# MPPT-LTC4162-F.net
KiCad netlist of a schematic drawn in EAGLE
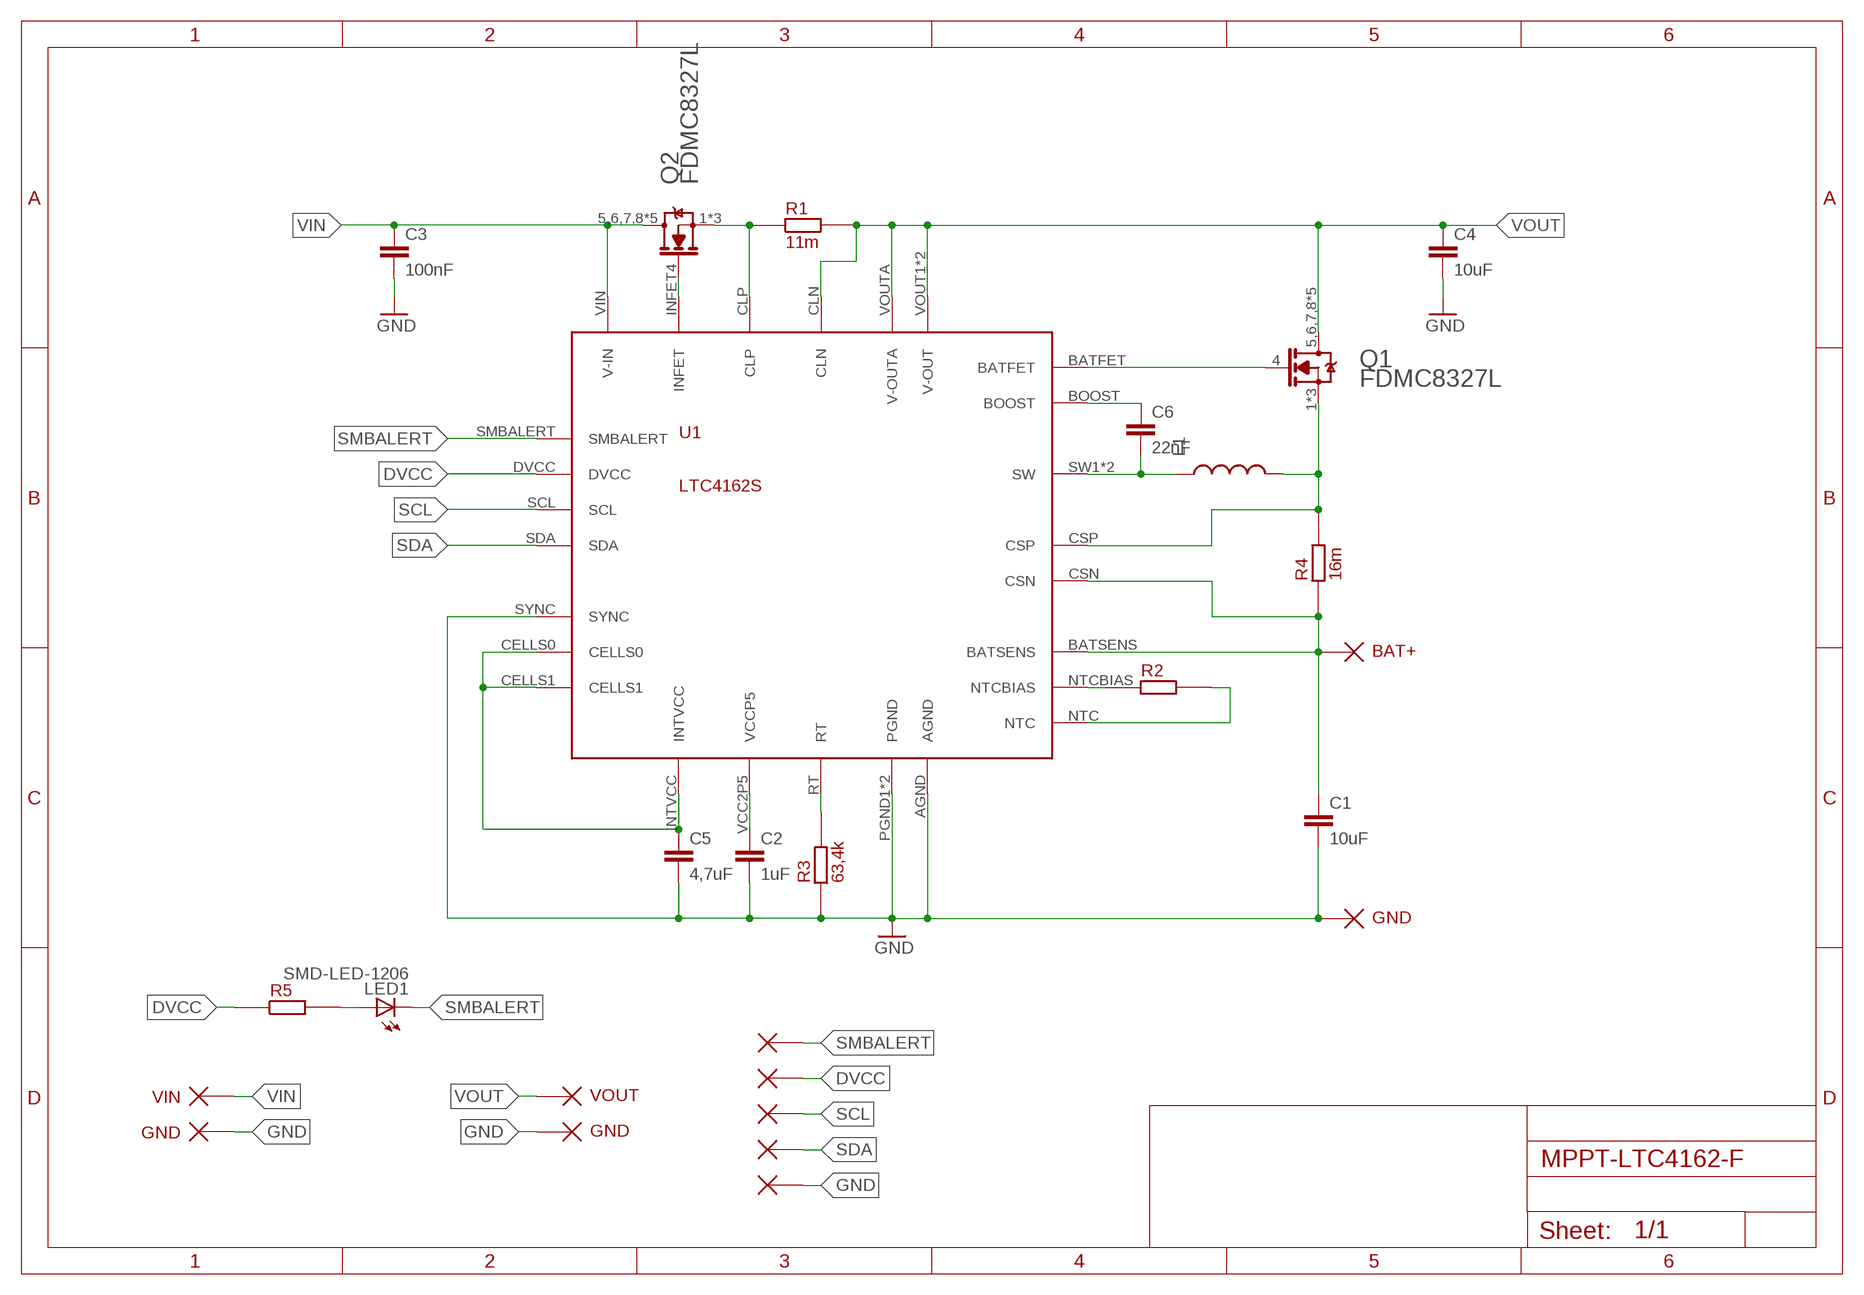
[diagram p0: schematic, sheet 1]

(export (version "E")
  (design (tool "Eeschema 10.0.6"))
  (components
    (comp (ref "C1")
      (value "10uF")
      (footprint "eagle-import:C1206")
      (libsource (lib "eagle-import") (part "SMD-C-1206"))
    )
    (comp (ref "C2")
      (value "1uF")
      (footprint "eagle-import:C1206")
      (libsource (lib "eagle-import") (part "SMD-C-1206"))
    )
    (comp (ref "C3")
      (value "100nF")
      (footprint "eagle-import:C1206")
      (libsource (lib "eagle-import") (part "SMD-C-1206"))
    )
    (comp (ref "C4")
      (value "10uF")
      (footprint "eagle-import:C1206")
      (libsource (lib "eagle-import") (part "SMD-C-1206"))
    )
    (comp (ref "C5")
      (value "4,7uF")
      (footprint "eagle-import:C1206")
      (libsource (lib "eagle-import") (part "SMD-C-1206"))
    )
    (comp (ref "C6")
      (value "22nF")
      (footprint "eagle-import:C1206")
      (libsource (lib "eagle-import") (part "SMD-C-1206"))
    )
    (comp (ref "L1")
      (value "L-242408FPS")
      (footprint "eagle-import:L-SMD-FPD")
      (libsource (lib "eagle-import") (part "L-242408FPS"))
    )
    (comp (ref "LED1")
      (value "SMD-LED-1206")
      (footprint "eagle-import:LED_1206")
      (libsource (lib "eagle-import") (part "SMD-LED-1206"))
    )
    (comp (ref "P1")
      (value "VIN")
      (footprint "eagle-import:PIN")
      (libsource (lib "eagle-import") (part "PIN"))
    )
    (comp (ref "P2")
      (value "GND")
      (footprint "eagle-import:PIN")
      (libsource (lib "eagle-import") (part "PIN"))
    )
    (comp (ref "P3")
      (value "PIN")
      (footprint "eagle-import:PIN")
      (libsource (lib "eagle-import") (part "PIN"))
    )
    (comp (ref "P4")
      (value "PIN")
      (footprint "eagle-import:PIN")
      (libsource (lib "eagle-import") (part "PIN"))
    )
    (comp (ref "P5")
      (value "PIN")
      (footprint "eagle-import:PIN")
      (libsource (lib "eagle-import") (part "PIN"))
    )
    (comp (ref "P6")
      (value "PIN")
      (footprint "eagle-import:PIN")
      (libsource (lib "eagle-import") (part "PIN"))
    )
    (comp (ref "P7")
      (value "GND")
      (footprint "eagle-import:PIN")
      (libsource (lib "eagle-import") (part "PIN"))
    )
    (comp (ref "P8")
      (value "BAT+")
      (footprint "eagle-import:PIN")
      (libsource (lib "eagle-import") (part "PIN"))
    )
    (comp (ref "P9")
      (value "VOUT")
      (footprint "eagle-import:PIN")
      (libsource (lib "eagle-import") (part "PIN"))
    )
    (comp (ref "P10")
      (value "GND")
      (footprint "eagle-import:PIN")
      (libsource (lib "eagle-import") (part "PIN"))
    )
    (comp (ref "P11")
      (value "PIN")
      (footprint "eagle-import:PIN")
      (libsource (lib "eagle-import") (part "PIN"))
    )
    (comp (ref "Q1")
      (value "N-MOSFET_FDMC8327LFDMC8327L")
      (footprint "eagle-import:ON_SEMI_FDMC8327L_0")
      (fields
        (field (name "DIGIKEY_PART_NUMBER") "FDMC8327LCT-ND")
        (field (name "MF") "ON Semi")
        (field (name "MOUSER_PART_NUMBER") "512-FDMC8327L")
      )
      (libsource (lib "eagle-import") (part "N-MOSFET_FDMC8327LFDMC8327L"))
    )
    (comp (ref "Q2")
      (value "N-MOSFET_FDMC8327LFDMC8327L")
      (footprint "eagle-import:ON_SEMI_FDMC8327L_0")
      (fields
        (field (name "DIGIKEY_PART_NUMBER") "FDMC8327LCT-ND")
        (field (name "MF") "ON Semi")
        (field (name "MOUSER_PART_NUMBER") "512-FDMC8327L")
      )
      (libsource (lib "eagle-import") (part "N-MOSFET_FDMC8327LFDMC8327L"))
    )
    (comp (ref "R1")
      (value "11m")
      (footprint "eagle-import:C1206")
      (libsource (lib "eagle-import") (part "SMD-RR1206"))
    )
    (comp (ref "R2")
      (value "SMD-RR1206")
      (footprint "eagle-import:C1206")
      (libsource (lib "eagle-import") (part "SMD-RR1206"))
    )
    (comp (ref "R3")
      (value "63,4k")
      (footprint "eagle-import:C1206")
      (libsource (lib "eagle-import") (part "SMD-RR1206"))
    )
    (comp (ref "R4")
      (value "16m")
      (footprint "eagle-import:C1206")
      (libsource (lib "eagle-import") (part "SMD-RR1206"))
    )
    (comp (ref "R5")
      (value "SMD-RR0603")
      (footprint "eagle-import:R0603")
      (libsource (lib "eagle-import") (part "SMD-RR0603"))
    )
    (comp (ref "U1")
      (value "LTC4162S")
      (footprint "eagle-import:QFN28-4X5MM")
      (libsource (lib "eagle-import") (part "LTC4162-F"))
    )
  )
  (nets
    (net (code "1") (name "DVCC") (class "Default")
      (node (ref "P4") (pin "P$1") (pinfunction "P$1_P$1") (pintype "bidirectional"))
      (node (ref "R5") (pin "1") (pinfunction "P$1_1") (pintype "passive"))
      (node (ref "U1") (pin "DVCC") (pinfunction "DVCC_DVCC") (pintype "bidirectional"))
    )
    (net (code "2") (name "GND") (class "Default")
      (node (ref "C1") (pin "2") (pinfunction "2_2") (pintype "passive"))
      (node (ref "C2") (pin "2") (pinfunction "2_2") (pintype "passive"))
      (node (ref "C3") (pin "2") (pinfunction "2_2") (pintype "passive"))
      (node (ref "C4") (pin "2") (pinfunction "2_2") (pintype "passive"))
      (node (ref "C5") (pin "2") (pinfunction "2_2") (pintype "passive"))
      (node (ref "P10") (pin "P$1") (pinfunction "P$1_P$1") (pintype "bidirectional"))
      (node (ref "P11") (pin "P$1") (pinfunction "P$1_P$1") (pintype "bidirectional"))
      (node (ref "P2") (pin "P$1") (pinfunction "P$1_P$1") (pintype "bidirectional"))
      (node (ref "P7") (pin "P$1") (pinfunction "P$1_P$1") (pintype "bidirectional"))
      (node (ref "R3") (pin "1") (pinfunction "P$1_1") (pintype "passive"))
      (node (ref "U1") (pin "AGND") (pinfunction "AGND_AGND") (pintype "bidirectional"))
      (node (ref "U1") (pin "PGND1") (pinfunction "PGND_PGND1") (pintype "bidirectional"))
      (node (ref "U1") (pin "PGND2") (pinfunction "PGND_PGND2") (pintype "bidirectional"))
      (node (ref "U1") (pin "SYNC") (pinfunction "SYNC_SYNC") (pintype "bidirectional"))
    )
    (net (code "3") (name "Net-(C5-Pad1)") (class "Default")
      (node (ref "C5") (pin "1") (pinfunction "1_1") (pintype "passive"))
      (node (ref "U1") (pin "CELLS0") (pinfunction "CELLS0_CELLS0") (pintype "bidirectional"))
      (node (ref "U1") (pin "CELLS1") (pinfunction "CELLS1_CELLS1") (pintype "bidirectional"))
      (node (ref "U1") (pin "INTVCC") (pinfunction "INTVCC_INTVCC") (pintype "bidirectional"))
    )
    (net (code "4") (name "Net-(C6-Pad1)") (class "Default")
      (node (ref "C6") (pin "1") (pinfunction "1_1") (pintype "passive"))
      (node (ref "U1") (pin "BOOST") (pinfunction "BOOST_BOOST") (pintype "bidirectional"))
    )
    (net (code "5") (name "Net-(C6-Pad2)") (class "Default")
      (node (ref "C6") (pin "2") (pinfunction "2_2") (pintype "passive"))
      (node (ref "L1") (pin "1") (pinfunction "1_1") (pintype "passive"))
      (node (ref "U1") (pin "SW1") (pinfunction "SW_SW1") (pintype "bidirectional"))
      (node (ref "U1") (pin "SW2") (pinfunction "SW_SW2") (pintype "bidirectional"))
    )
    (net (code "6") (name "Net-(Q1-G)") (class "Default")
      (node (ref "Q1") (pin "4") (pinfunction "G_4") (pintype "passive"))
      (node (ref "U1") (pin "BATFET") (pinfunction "BATFET_BATFET") (pintype "bidirectional"))
    )
    (net (code "7") (name "Net-(Q2-G)") (class "Default")
      (node (ref "Q2") (pin "4") (pinfunction "G_4") (pintype "passive"))
      (node (ref "U1") (pin "INFET") (pinfunction "INFET_INFET") (pintype "bidirectional"))
    )
    (net (code "8") (name "Net-(R1-P$1)") (class "Default")
      (node (ref "Q2") (pin "1") (pinfunction "1_S_1") (pintype "passive"))
      (node (ref "Q2") (pin "2") (pinfunction "1_S_2") (pintype "passive"))
      (node (ref "Q2") (pin "3") (pinfunction "1_S_3") (pintype "passive"))
      (node (ref "R1") (pin "1") (pinfunction "P$1_1") (pintype "passive"))
      (node (ref "U1") (pin "CLP") (pinfunction "CLP_CLP") (pintype "bidirectional"))
    )
    (net (code "9") (name "Net-(R2-P$1)") (class "Default")
      (node (ref "R2") (pin "1") (pinfunction "P$1_1") (pintype "passive"))
      (node (ref "U1") (pin "NTCBIAS") (pinfunction "NTCBIAS_NTCBIAS") (pintype "bidirectional"))
    )
    (net (code "10") (name "Net-(R2-P$3)") (class "Default")
      (node (ref "R2") (pin "2") (pinfunction "P$3_2") (pintype "passive"))
      (node (ref "U1") (pin "NTC") (pinfunction "NTC_NTC") (pintype "bidirectional"))
    )
    (net (code "11") (name "Net-(R3-P$3)") (class "Default")
      (node (ref "R3") (pin "2") (pinfunction "P$3_2") (pintype "passive"))
      (node (ref "U1") (pin "RT") (pinfunction "RT_RT") (pintype "bidirectional"))
    )
    (net (code "12") (name "Net-(R4-P$1)") (class "Default")
      (node (ref "C1") (pin "1") (pinfunction "1_1") (pintype "passive"))
      (node (ref "P8") (pin "P$1") (pinfunction "P$1_P$1") (pintype "bidirectional"))
      (node (ref "R4") (pin "1") (pinfunction "P$1_1") (pintype "passive"))
      (node (ref "U1") (pin "BATSENS") (pinfunction "BATSENS_BATSENS") (pintype "bidirectional"))
      (node (ref "U1") (pin "CSN") (pinfunction "CSN_CSN") (pintype "bidirectional"))
    )
    (net (code "13") (name "Net-(R4-P$3)") (class "Default")
      (node (ref "L1") (pin "2") (pinfunction "2_2") (pintype "passive"))
      (node (ref "Q1") (pin "1") (pinfunction "1_S_1") (pintype "passive"))
      (node (ref "Q1") (pin "2") (pinfunction "1_S_2") (pintype "passive"))
      (node (ref "Q1") (pin "3") (pinfunction "1_S_3") (pintype "passive"))
      (node (ref "R4") (pin "2") (pinfunction "P$3_2") (pintype "passive"))
      (node (ref "U1") (pin "CSP") (pinfunction "CSP_CSP") (pintype "bidirectional"))
    )
    (net (code "14") (name "Net-(R5-P$3)") (class "Default")
      (node (ref "LED1") (pin "A") (pinfunction "A_A") (pintype "passive"))
      (node (ref "R5") (pin "2") (pinfunction "P$3_2") (pintype "passive"))
    )
    (net (code "15") (name "Net-(U1-VCCP5)") (class "Default")
      (node (ref "C2") (pin "1") (pinfunction "1_1") (pintype "passive"))
      (node (ref "U1") (pin "VCC2P5") (pinfunction "VCCP5_VCC2P5") (pintype "bidirectional"))
    )
    (net (code "16") (name "SCL") (class "Default")
      (node (ref "P5") (pin "P$1") (pinfunction "P$1_P$1") (pintype "bidirectional"))
      (node (ref "U1") (pin "SCL") (pinfunction "SCL_SCL") (pintype "bidirectional"))
    )
    (net (code "17") (name "SDA") (class "Default")
      (node (ref "P6") (pin "P$1") (pinfunction "P$1_P$1") (pintype "bidirectional"))
      (node (ref "U1") (pin "SDA") (pinfunction "SDA_SDA") (pintype "bidirectional"))
    )
    (net (code "18") (name "SMBALERT") (class "Default")
      (node (ref "LED1") (pin "C") (pinfunction "C_C") (pintype "passive"))
      (node (ref "P3") (pin "P$1") (pinfunction "P$1_P$1") (pintype "bidirectional"))
      (node (ref "U1") (pin "SMBALERT") (pinfunction "SMBALERT_SMBALERT") (pintype "bidirectional"))
    )
    (net (code "19") (name "VIN") (class "Default")
      (node (ref "C3") (pin "1") (pinfunction "1_1") (pintype "passive"))
      (node (ref "P1") (pin "P$1") (pinfunction "P$1_P$1") (pintype "bidirectional"))
      (node (ref "Q2") (pin "5,6,7,8") (pinfunction "D_5,6,7,8") (pintype "passive"))
      (node (ref "Q2") (pin "5,6,7,8-2") (pinfunction "D_5,6,7,8-2") (pintype "passive"))
      (node (ref "Q2") (pin "5,6,7,8-3") (pinfunction "D_5,6,7,8-3") (pintype "passive"))
      (node (ref "Q2") (pin "5,6,7,8-4") (pinfunction "D_5,6,7,8-4") (pintype "passive"))
      (node (ref "Q2") (pin "5,6,7,8-5") (pinfunction "D_5,6,7,8-5") (pintype "passive"))
      (node (ref "U1") (pin "VIN") (pinfunction "V-IN_VIN") (pintype "bidirectional"))
    )
    (net (code "20") (name "VOUT") (class "Default")
      (node (ref "C4") (pin "1") (pinfunction "1_1") (pintype "passive"))
      (node (ref "P9") (pin "P$1") (pinfunction "P$1_P$1") (pintype "bidirectional"))
      (node (ref "Q1") (pin "5,6,7,8") (pinfunction "D_5,6,7,8") (pintype "passive"))
      (node (ref "Q1") (pin "5,6,7,8-2") (pinfunction "D_5,6,7,8-2") (pintype "passive"))
      (node (ref "Q1") (pin "5,6,7,8-3") (pinfunction "D_5,6,7,8-3") (pintype "passive"))
      (node (ref "Q1") (pin "5,6,7,8-4") (pinfunction "D_5,6,7,8-4") (pintype "passive"))
      (node (ref "Q1") (pin "5,6,7,8-5") (pinfunction "D_5,6,7,8-5") (pintype "passive"))
      (node (ref "R1") (pin "2") (pinfunction "P$3_2") (pintype "passive"))
      (node (ref "U1") (pin "CLN") (pinfunction "CLN_CLN") (pintype "bidirectional"))
      (node (ref "U1") (pin "VOUT1") (pinfunction "V-OUT_VOUT1") (pintype "bidirectional"))
      (node (ref "U1") (pin "VOUT2") (pinfunction "V-OUT_VOUT2") (pintype "bidirectional"))
      (node (ref "U1") (pin "VOUTA") (pinfunction "V-OUTA_VOUTA") (pintype "bidirectional"))
    )
  )
)
